# photon_VTspy.net
KiCad netlist of a schematic drawn in EAGLE
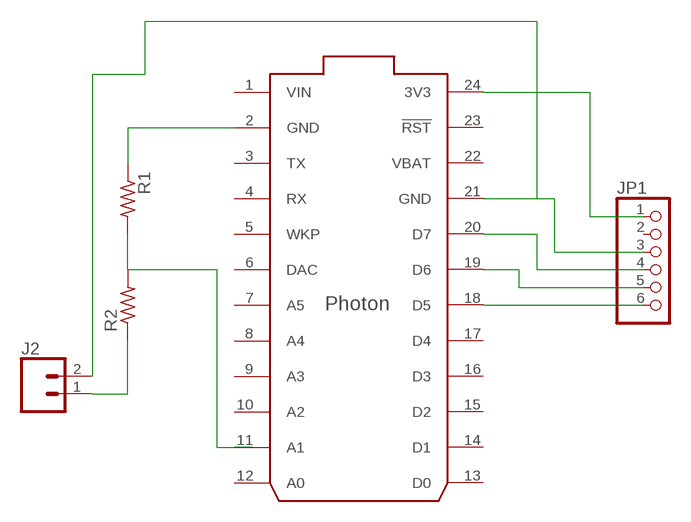
[diagram p0: schematic, sheet 1]

(export (version "E")
  (design (tool "Eeschema 10.0.6"))
  (components
    (comp (ref "J2")
      (value "CONN_023.5MM")
      (footprint "eagle-import:SCREWTERMINAL-3.5MM-2")
      (libsource (lib "eagle-import") (part "CONN_023.5MM"))
    )
    (comp (ref "JP1")
      (value "PINHD-1X6")
      (footprint "eagle-import:1X06")
      (libsource (lib "eagle-import") (part "PINHD-1X6"))
    )
    (comp (ref "R1")
      (value "R-US_0207/10")
      (footprint "eagle-import:0207_10")
      (libsource (lib "eagle-import") (part "R-US_0207/10"))
    )
    (comp (ref "R2")
      (value "R-US_0207/10")
      (footprint "eagle-import:0207_10")
      (libsource (lib "eagle-import") (part "R-US_0207/10"))
    )
    (comp (ref "U$1")
      (value "PHOTON_WITH_HEADERS")
      (footprint "eagle-import:PHOTON")
      (libsource (lib "eagle-import") (part "PHOTON_WITH_HEADERS"))
    )
  )
  (nets
    (net (code "1") (name "/VBAT") (class "Default")
      (node (ref "U$1") (pin "22") (pinfunction "VBAT_22") (pintype "power_in"))
    )
    (net (code "2") (name "/VIN") (class "Default")
      (node (ref "U$1") (pin "1") (pinfunction "VIN_1") (pintype "power_in"))
    )
    (net (code "3") (name "Net-(J2-Pad1)") (class "Default")
      (node (ref "J2") (pin "1") (pinfunction "1_1") (pintype "passive"))
      (node (ref "R2") (pin "1") (pinfunction "1_1") (pintype "passive"))
    )
    (net (code "4") (name "Net-(J2-Pad2)") (class "Default")
      (node (ref "J2") (pin "2") (pinfunction "2_2") (pintype "passive"))
      (node (ref "JP1") (pin "3") (pinfunction "3_3") (pintype "passive"))
      (node (ref "U$1") (pin "21") (pinfunction "GND_21") (pintype "power_in"))
    )
    (net (code "5") (name "Net-(R1-Pad1)") (class "Default")
      (node (ref "R1") (pin "1") (pinfunction "1_1") (pintype "passive"))
      (node (ref "U$1") (pin "2") (pinfunction "GND_2") (pintype "power_in"))
    )
    (net (code "6") (name "Net-(U$1-3V3)") (class "Default")
      (node (ref "JP1") (pin "1") (pinfunction "1_1") (pintype "passive"))
      (node (ref "U$1") (pin "24") (pinfunction "3V3_24") (pintype "power_in"))
    )
    (net (code "7") (name "Net-(U$1-A1)") (class "Default")
      (node (ref "R1") (pin "2") (pinfunction "2_2") (pintype "passive"))
      (node (ref "R2") (pin "2") (pinfunction "2_2") (pintype "passive"))
      (node (ref "U$1") (pin "11") (pinfunction "A1_11") (pintype "bidirectional"))
    )
    (net (code "8") (name "Net-(U$1-D5)") (class "Default")
      (node (ref "JP1") (pin "6") (pinfunction "6_6") (pintype "passive"))
      (node (ref "U$1") (pin "18") (pinfunction "D5_18") (pintype "bidirectional"))
    )
    (net (code "9") (name "Net-(U$1-D6)") (class "Default")
      (node (ref "JP1") (pin "5") (pinfunction "5_5") (pintype "passive"))
      (node (ref "U$1") (pin "19") (pinfunction "D6_19") (pintype "bidirectional"))
    )
    (net (code "10") (name "Net-(U$1-D7)") (class "Default")
      (node (ref "JP1") (pin "4") (pinfunction "4_4") (pintype "passive"))
      (node (ref "U$1") (pin "20") (pinfunction "D7_20") (pintype "bidirectional"))
    )
    (net (code "11") (name "unconnected-(JP1-Pad2)") (class "Default")
      (node (ref "JP1") (pin "2") (pinfunction "2_2") (pintype "passive"))
    )
    (net (code "12") (name "unconnected-(U$1-A0-Pad12)") (class "Default")
      (node (ref "U$1") (pin "12") (pinfunction "A0_12") (pintype "bidirectional"))
    )
    (net (code "13") (name "unconnected-(U$1-A2-Pad10)") (class "Default")
      (node (ref "U$1") (pin "10") (pinfunction "A2_10") (pintype "bidirectional"))
    )
    (net (code "14") (name "unconnected-(U$1-A3-Pad9)") (class "Default")
      (node (ref "U$1") (pin "9") (pinfunction "A3_9") (pintype "bidirectional"))
    )
    (net (code "15") (name "unconnected-(U$1-A4-Pad8)") (class "Default")
      (node (ref "U$1") (pin "8") (pinfunction "A4_8") (pintype "bidirectional"))
    )
    (net (code "16") (name "unconnected-(U$1-A5-Pad7)") (class "Default")
      (node (ref "U$1") (pin "7") (pinfunction "A5_7") (pintype "bidirectional"))
    )
    (net (code "17") (name "unconnected-(U$1-D0-Pad13)") (class "Default")
      (node (ref "U$1") (pin "13") (pinfunction "D0_13") (pintype "bidirectional"))
    )
    (net (code "18") (name "unconnected-(U$1-D1-Pad14)") (class "Default")
      (node (ref "U$1") (pin "14") (pinfunction "D1_14") (pintype "bidirectional"))
    )
    (net (code "19") (name "unconnected-(U$1-D2-Pad15)") (class "Default")
      (node (ref "U$1") (pin "15") (pinfunction "D2_15") (pintype "bidirectional"))
    )
    (net (code "20") (name "unconnected-(U$1-D3-Pad16)") (class "Default")
      (node (ref "U$1") (pin "16") (pinfunction "D3_16") (pintype "bidirectional"))
    )
    (net (code "21") (name "unconnected-(U$1-D4-Pad17)") (class "Default")
      (node (ref "U$1") (pin "17") (pinfunction "D4_17") (pintype "bidirectional"))
    )
    (net (code "22") (name "unconnected-(U$1-DAC-Pad6)") (class "Default")
      (node (ref "U$1") (pin "6") (pinfunction "DAC_6") (pintype "bidirectional"))
    )
    (net (code "23") (name "unconnected-(U$1-RX-Pad4)") (class "Default")
      (node (ref "U$1") (pin "4") (pinfunction "RX_4") (pintype "bidirectional"))
    )
    (net (code "24") (name "unconnected-(U$1-TX-Pad3)") (class "Default")
      (node (ref "U$1") (pin "3") (pinfunction "TX_3") (pintype "bidirectional"))
    )
    (net (code "25") (name "unconnected-(U$1-WKP-Pad5)") (class "Default")
      (node (ref "U$1") (pin "5") (pinfunction "WKP_5") (pintype "bidirectional"))
    )
    (net (code "26") (name "unconnected-(U$1-~{RST}-Pad23)") (class "Default")
      (node (ref "U$1") (pin "23") (pinfunction "~{RST}_23") (pintype "bidirectional"))
    )
  )
)
